# 2018_LedWhite.net
KiCad netlist of a schematic drawn in Altium Designer
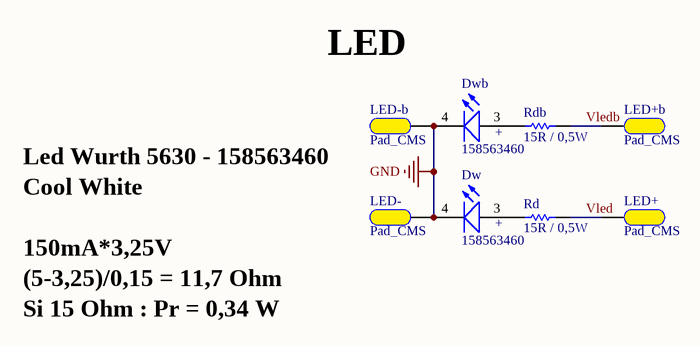
[diagram p0: 2018_LedWhite.SchDoc]

(export (version "E")
  (design (tool "Eeschema 10.0.6"))
  (components
    (comp (ref "Dw")
      (value "158563460")
      (footprint "WL-SWTP_5630")
      (description "WL-SWTP SMD White Top view PLCC, size 5630, Cool White")
      (fields (field (name "PUBLISHER") "Wurth Elektronik"))
      (libsource (lib "ALTIUM-WL-SWTP") (part "158563460"))
    )
    (comp (ref "Dwb")
      (value "158563460")
      (footprint "WL-SWTP_5630")
      (description "WL-SWTP SMD White Top view PLCC, size 5630, Cool White")
      (fields (field (name "PUBLISHER") "Wurth Elektronik"))
      (libsource (lib "ALTIUM-WL-SWTP") (part "158563460"))
    )
    (comp (ref "LED+")
      (value "Pad_CMS")
      (footprint "PAD_CMS_5.08x2.54")
      (description "Pad pour souder un fil")
      (fields (field (name "PUBLISHER") "Damien Guitton"))
      (libsource (lib "DG_Connecteur") (part "Pad_CMS"))
    )
    (comp (ref "LED+b")
      (value "Pad_CMS")
      (footprint "PAD_CMS_5.08x2.54")
      (description "Pad pour souder un fil")
      (fields (field (name "PUBLISHER") "Damien Guitton"))
      (libsource (lib "DG_Connecteur") (part "Pad_CMS"))
    )
    (comp (ref "LED-")
      (value "Pad_CMS")
      (footprint "PAD_CMS_5.08x2.54")
      (description "Pad pour souder un fil")
      (fields (field (name "PUBLISHER") "Damien Guitton"))
      (libsource (lib "DG_Connecteur") (part "Pad_CMS"))
    )
    (comp (ref "LED-b")
      (value "Pad_CMS")
      (footprint "PAD_CMS_5.08x2.54")
      (description "Pad pour souder un fil")
      (fields (field (name "PUBLISHER") "Damien Guitton"))
      (libsource (lib "DG_Connecteur") (part "Pad_CMS"))
    )
    (comp (ref "Rd")
      (value "15R / 0,5W")
      (footprint "R1206_N")
      (description "Resistor")
      (fields (field (name "PUBLISHER") "Altium Limited"))
      (libsource (lib "_ROBOT") (part "Resistor"))
    )
    (comp (ref "Rdb")
      (value "15R / 0,5W")
      (footprint "R1206_N")
      (description "Resistor")
      (fields (field (name "PUBLISHER") "Altium Limited"))
      (libsource (lib "_ROBOT") (part "Resistor"))
    )
  )
  (nets
    (net (code "1") (name "/Vled") (class "Default")
      (node (ref "LED+") (pin "1") (pinfunction "1_1") (pintype "passive"))
      (node (ref "Rd") (pin "2") (pinfunction "2_2") (pintype "passive"))
    )
    (net (code "2") (name "/Vledb") (class "Default")
      (node (ref "LED+b") (pin "1") (pinfunction "1_1") (pintype "passive"))
      (node (ref "Rdb") (pin "2") (pinfunction "2_2") (pintype "passive"))
    )
    (net (code "3") (name "GND") (class "Default")
      (node (ref "Dw") (pin "4") (pinfunction "K_4") (pintype "passive"))
      (node (ref "Dwb") (pin "4") (pinfunction "K_4") (pintype "passive"))
      (node (ref "LED-") (pin "1") (pinfunction "1_1") (pintype "passive"))
      (node (ref "LED-b") (pin "1") (pinfunction "1_1") (pintype "passive"))
    )
    (net (code "4") (name "Net-(Dw-A)") (class "Default")
      (node (ref "Dw") (pin "3") (pinfunction "A_3") (pintype "passive"))
      (node (ref "Rd") (pin "1") (pinfunction "1_1") (pintype "passive"))
    )
    (net (code "5") (name "Net-(Dwb-A)") (class "Default")
      (node (ref "Dwb") (pin "3") (pinfunction "A_3") (pintype "passive"))
      (node (ref "Rdb") (pin "1") (pinfunction "1_1") (pintype "passive"))
    )
  )
)
